# SCH_ATMEGA328_GAZPAR_rev1_0b.net
KiCad netlist of a schematic drawn in EasyEDA
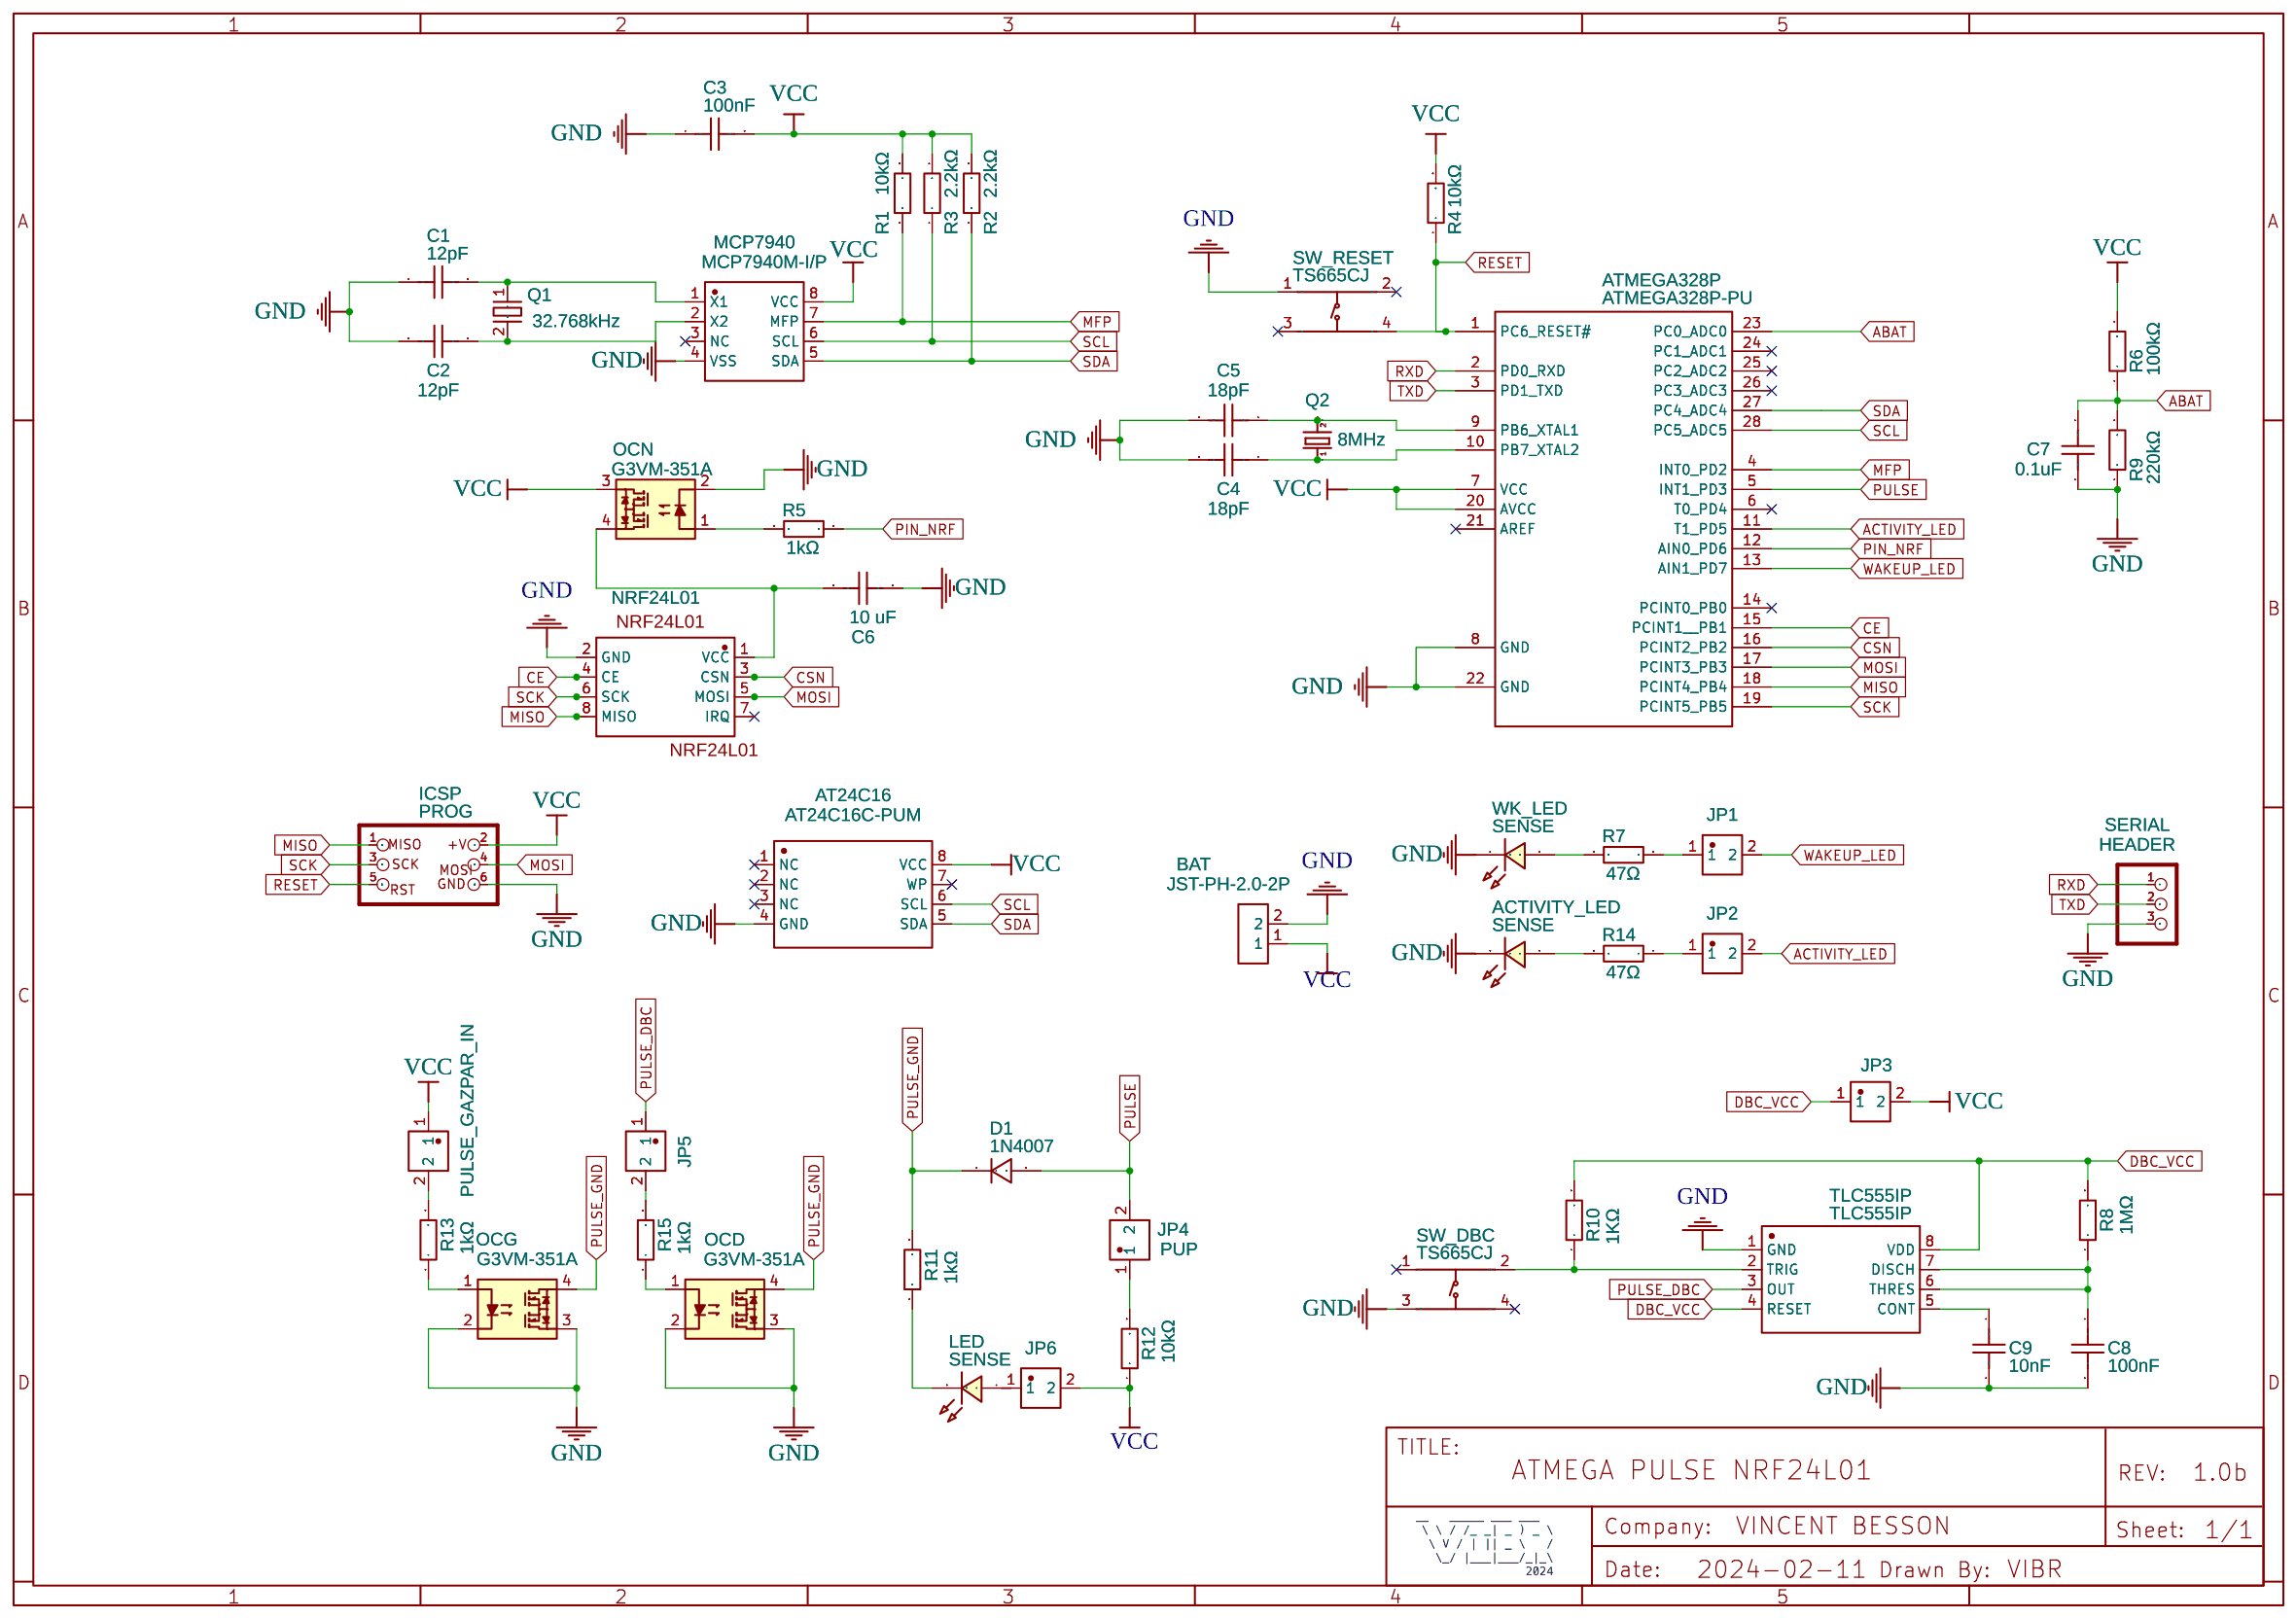
[diagram p0: schematic sheet]

(export (version "E")
  (design (tool "Eeschema 10.0.6"))
  (components
    (comp (ref "ACTIVITY_LED")
      (value "SENSE")
      (fields
        (field (name "Manufacturer Part") "333-2SURD/S530-A3")
        (field (name "Manufacturer") "EVERLIGHT(台湾亿光)")
      )
      (libsource (lib "") (part "LED-TH-5mm_R_2"))
    )
    (comp (ref "AT24C16")
      (value "AT24C16C-PUM")
      (fields (field (name "Manufacturer") "MICROCHIP(美国微芯)"))
      (libsource (lib "") (part "AT24C16C-PUM"))
    )
    (comp (ref "ATMEGA328P")
      (value "ATMEGA328P-PU")
      (fields (field (name "Manufacturer") "MICROCHIP(美国微芯)"))
      (libsource (lib "") (part "ATMEGA328P-PU"))
    )
    (comp (ref "BAT") (value "JST-PH-2.0-2P") (libsource (lib "") (part "JST-PH-2.0-2P")))
    (comp (ref "C1")
      (value "12pF")
      (fields
        (field (name "Manufacturer Part") "CC1H200KA1PDCH4B3003")
        (field (name "Manufacturer") "Dersonic(德尔创)")
      )
      (libsource (lib "") (part "CC1H200KA1PDCH4B3003"))
    )
    (comp (ref "C2")
      (value "12pF")
      (fields
        (field (name "Manufacturer Part") "CC1H200KA1PDCH4B3003")
        (field (name "Manufacturer") "Dersonic(德尔创)")
      )
      (libsource (lib "") (part "CC1H200KA1PDCH4B3003_1"))
    )
    (comp (ref "C3")
      (value "100nF")
      (fields
        (field (name "Manufacturer Part") "CC1H200KA1PDCH4B3003")
        (field (name "Manufacturer") "Dersonic(德尔创)")
      )
      (libsource (lib "") (part "CC1H200KA1PDCH4B3003"))
    )
    (comp (ref "C4")
      (value "18pF")
      (fields
        (field (name "Manufacturer Part") "CC1H200KA1PDCH4B3003")
        (field (name "Manufacturer") "Dersonic(德尔创)")
      )
      (libsource (lib "") (part "CC1H200KA1PDCH4B3003_1"))
    )
    (comp (ref "C5")
      (value "18pF")
      (fields
        (field (name "Manufacturer Part") "CC1H200KA1PDCH4B3003")
        (field (name "Manufacturer") "Dersonic(德尔创)")
      )
      (libsource (lib "") (part "CC1H200KA1PDCH4B3003_1"))
    )
    (comp (ref "C6")
      (value "10 uF")
      (fields
        (field (name "Manufacturer Part") "CC1H200KA1PDCH4B3003")
        (field (name "Manufacturer") "Dersonic(德尔创)")
      )
      (libsource (lib "") (part "CC1H200KA1PDCH4B3003"))
    )
    (comp (ref "C7")
      (value "0.1uF")
      (fields
        (field (name "Manufacturer Part") "CC1H200KA1PDCH4B3003")
        (field (name "Manufacturer") "Dersonic(德尔创)")
      )
      (libsource (lib "") (part "CC1H200KA1PDCH4B3003_2"))
    )
    (comp (ref "C8")
      (value "100nF")
      (fields
        (field (name "Manufacturer Part") "CC1H200KA1PDCH4B3003")
        (field (name "Manufacturer") "Dersonic(德尔创)")
      )
      (libsource (lib "") (part "CC1H200KA1PDCH4B3003_2"))
    )
    (comp (ref "C9")
      (value "10nF")
      (fields
        (field (name "Manufacturer Part") "CC1H200KA1PDCH4B3003")
        (field (name "Manufacturer") "Dersonic(德尔创)")
      )
      (libsource (lib "") (part "CC1H200KA1PDCH4B3003_2"))
    )
    (comp (ref "D1")
      (value "1N4007")
      (fields (field (name "Manufacturer") "SEMTECH"))
      (libsource (lib "") (part "1N4007"))
    )
    (comp (ref "ICSP") (value "PROG") (libsource (lib "") (part "CON_HEADER_PRG_AVR_ICSP-PTH")))
    (comp (ref "JP1")
      (value "GAZPAR")
      (fields
        (field (name "Manufacturer Part") "X6521WV-2x01H-C30D60")
        (field (name "Manufacturer") "XKB Connectivity(中国星坤)")
      )
      (libsource (lib "") (part "X6521WV-2X01H-C30D60_1"))
    )
    (comp (ref "JP2")
      (value "GAZPAR")
      (fields
        (field (name "Manufacturer Part") "X6521WV-2x01H-C30D60")
        (field (name "Manufacturer") "XKB Connectivity(中国星坤)")
      )
      (libsource (lib "") (part "X6521WV-2X01H-C30D60_1"))
    )
    (comp (ref "JP3")
      (value "GAZPAR")
      (fields
        (field (name "Manufacturer Part") "X6521WV-2x01H-C30D60")
        (field (name "Manufacturer") "XKB Connectivity(中国星坤)")
      )
      (libsource (lib "") (part "X6521WV-2X01H-C30D60_1"))
    )
    (comp (ref "JP4")
      (value "PUP")
      (fields
        (field (name "Manufacturer Part") "X6521WV-2x01H-C30D60")
        (field (name "Manufacturer") "XKB Connectivity(中国星坤)")
      )
      (libsource (lib "") (part "X6521WV-2X01H-C30D60"))
    )
    (comp (ref "JP5")
      (value "GAZPAR_PULSE")
      (fields
        (field (name "Manufacturer Part") "X6521WV-2x01H-C30D60")
        (field (name "Manufacturer") "XKB Connectivity(中国星坤)")
      )
      (libsource (lib "") (part "X6521WV-2X01H-C30D60_3"))
    )
    (comp (ref "JP6")
      (value "JMP_LED")
      (fields
        (field (name "Manufacturer Part") "X6521WV-2x01H-C30D60")
        (field (name "Manufacturer") "XKB Connectivity(中国星坤)")
      )
      (libsource (lib "") (part "X6521WV-2X01H-C30D60_1"))
    )
    (comp (ref "LED")
      (value "SENSE")
      (fields
        (field (name "Manufacturer Part") "333-2SURD/S530-A3")
        (field (name "Manufacturer") "EVERLIGHT(台湾亿光)")
      )
      (libsource (lib "") (part "LED-TH-5mm_R_1"))
    )
    (comp (ref "MCP7940")
      (value "MCP7940M-I/P")
      (fields (field (name "Manufacturer") "MICROCHIP(美国微芯)"))
      (libsource (lib "") (part "MCP7940M-I/P"))
    )
    (comp (ref "NRF24L01") (value "NRF24L01") (libsource (lib "") (part "NRF24L01")))
    (comp (ref "OCD") (value "G3VM-351A") (libsource (lib "") (part "G3VM-351A_1")))
    (comp (ref "OCG") (value "G3VM-351A") (libsource (lib "") (part "G3VM-351A")))
    (comp (ref "OCN") (value "G3VM-351A") (libsource (lib "") (part "G3VM-351A_2")))
    (comp (ref "PULSE_GAZPAR_IN")
      (value "GAZPAR_PULSE")
      (fields
        (field (name "Manufacturer Part") "X6521WV-2x01H-C30D60")
        (field (name "Manufacturer") "XKB Connectivity(中国星坤)")
      )
      (libsource (lib "") (part "X6521WV-2X01H-C30D60_2"))
    )
    (comp (ref "Q1")
      (value "32.768kHz")
      (fields (field (name "Manufacturer Part") "AB26T-32.768KHZ") (field (name "Manufacturer") "ABRACON"))
      (libsource (lib "") (part "AB26T-32.768KHZ"))
    )
    (comp (ref "Q2") (value "8MHz") (libsource (lib "") (part "HC49/S1.3")))
    (comp (ref "R1")
      (value "10kΩ")
      (fields
        (field (name "Manufacturer Part") "MFR0W4F1002A50")
        (field (name "Manufacturer") "UNI-ROYAL(厚声)")
      )
      (libsource (lib "") (part "MFR0W4F1002A50_1"))
    )
    (comp (ref "R2")
      (value "2.2kΩ")
      (fields
        (field (name "Manufacturer Part") "MFR0W4F1002A50")
        (field (name "Manufacturer") "UNI-ROYAL(厚声)")
      )
      (libsource (lib "") (part "MFR0W4F1002A50_1"))
    )
    (comp (ref "R3")
      (value "2.2kΩ")
      (fields
        (field (name "Manufacturer Part") "MFR0W4F1002A50")
        (field (name "Manufacturer") "UNI-ROYAL(厚声)")
      )
      (libsource (lib "") (part "MFR0W4F1002A50_1"))
    )
    (comp (ref "R4")
      (value "10kΩ")
      (fields
        (field (name "Manufacturer Part") "MFR0W4F1002A50")
        (field (name "Manufacturer") "UNI-ROYAL(厚声)")
      )
      (libsource (lib "") (part "MFR0W4F1002A50_1"))
    )
    (comp (ref "R5")
      (value "1kΩ")
      (fields
        (field (name "Manufacturer Part") "MFR0W4F1002A50")
        (field (name "Manufacturer") "UNI-ROYAL(厚声)")
      )
      (libsource (lib "") (part "MFR0W4F1002A50"))
    )
    (comp (ref "R6")
      (value "100kΩ")
      (fields
        (field (name "Manufacturer Part") "MFR0W4F1002A50")
        (field (name "Manufacturer") "UNI-ROYAL(厚声)")
      )
      (libsource (lib "") (part "MFR0W4F1002A50_1"))
    )
    (comp (ref "R7")
      (value "47Ω")
      (fields
        (field (name "Manufacturer Part") "MFR0W4F1002A50")
        (field (name "Manufacturer") "UNI-ROYAL(厚声)")
      )
      (libsource (lib "") (part "MFR0W4F1002A50"))
    )
    (comp (ref "R8")
      (value "1MΩ")
      (fields
        (field (name "Manufacturer Part") "MFR0W4F1002A50")
        (field (name "Manufacturer") "UNI-ROYAL(厚声)")
      )
      (libsource (lib "") (part "MFR0W4F1002A50_1"))
    )
    (comp (ref "R9")
      (value "220kΩ")
      (fields
        (field (name "Manufacturer Part") "MFR0W4F1002A50")
        (field (name "Manufacturer") "UNI-ROYAL(厚声)")
      )
      (libsource (lib "") (part "MFR0W4F1002A50_1"))
    )
    (comp (ref "R10")
      (value "1KΩ")
      (fields
        (field (name "Manufacturer Part") "MFR0W4F1002A50")
        (field (name "Manufacturer") "UNI-ROYAL(厚声)")
      )
      (libsource (lib "") (part "MFR0W4F1002A50_1"))
    )
    (comp (ref "R11")
      (value "1kΩ")
      (fields
        (field (name "Manufacturer Part") "MFR0W4F1002A50")
        (field (name "Manufacturer") "UNI-ROYAL(厚声)")
      )
      (libsource (lib "") (part "MFR0W4F1002A50_1"))
    )
    (comp (ref "R12")
      (value "10kΩ")
      (fields
        (field (name "Manufacturer Part") "MFR0W4F1002A50")
        (field (name "Manufacturer") "UNI-ROYAL(厚声)")
      )
      (libsource (lib "") (part "MFR0W4F1002A50_1"))
    )
    (comp (ref "R13")
      (value "1kΩ")
      (fields
        (field (name "Manufacturer Part") "MFR0W4F1002A50")
        (field (name "Manufacturer") "UNI-ROYAL(厚声)")
      )
      (libsource (lib "") (part "MFR0W4F1002A50_1"))
    )
    (comp (ref "R14")
      (value "47Ω")
      (fields
        (field (name "Manufacturer Part") "MFR0W4F1002A50")
        (field (name "Manufacturer") "UNI-ROYAL(厚声)")
      )
      (libsource (lib "") (part "MFR0W4F1002A50"))
    )
    (comp (ref "R15")
      (value "1kΩ")
      (fields
        (field (name "Manufacturer Part") "MFR0W4F1002A50")
        (field (name "Manufacturer") "UNI-ROYAL(厚声)")
      )
      (libsource (lib "") (part "MFR0W4F1002A50_1"))
    )
    (comp (ref "SERIAL") (value "HEADER") (libsource (lib "") (part "PINHD-1X3")))
    (comp (ref "SW_DBC")
      (value "TS665CJ")
      (fields (field (name "Manufacturer") "SHOU HAN(首韩)"))
      (libsource (lib "") (part "TS665CJ_1"))
    )
    (comp (ref "SW_RESET")
      (value "TS665CJ")
      (fields (field (name "Manufacturer") "SHOU HAN(首韩)"))
      (libsource (lib "") (part "TS665CJ"))
    )
    (comp (ref "TLC555IP")
      (value "TLC555IP")
      (fields (field (name "Manufacturer") "TI(德州仪器)"))
      (libsource (lib "") (part "TLC555IP"))
    )
    (comp (ref "WK_LED")
      (value "SENSE")
      (fields
        (field (name "Manufacturer Part") "333-2SURD/S530-A3")
        (field (name "Manufacturer") "EVERLIGHT(台湾亿光)")
      )
      (libsource (lib "") (part "LED-TH-5mm_R"))
    )
  )
  (nets
    (net (code "1") (name "ABAT") (class "Default")
      (node (ref "ATMEGA328P") (pin "23") (pinfunction "PC0_ADC0_23") (pintype "bidirectional"))
      (node (ref "C7") (pin "1") (pinfunction "1_1") (pintype "unspecified"))
      (node (ref "R6") (pin "1") (pinfunction "1_1") (pintype "input"))
      (node (ref "R9") (pin "2") (pinfunction "2_2") (pintype "input"))
    )
    (net (code "2") (name "ACTIVITY_LED") (class "Default")
      (node (ref "ATMEGA328P") (pin "11") (pinfunction "T1_PD5_11") (pintype "bidirectional"))
      (node (ref "JP2") (pin "2") (pinfunction "2_2") (pintype "unspecified"))
    )
    (net (code "3") (name "CE") (class "Default")
      (node (ref "ATMEGA328P") (pin "15") (pinfunction "PCINT1__PB1_15") (pintype "bidirectional"))
      (node (ref "NRF24L01") (pin "4") (pinfunction "CE_4") (pintype "unspecified"))
    )
    (net (code "4") (name "CSN") (class "Default")
      (node (ref "ATMEGA328P") (pin "16") (pinfunction "PCINT2_PB2_16") (pintype "bidirectional"))
      (node (ref "NRF24L01") (pin "3") (pinfunction "CSN_3") (pintype "unspecified"))
    )
    (net (code "5") (name "DBC_VCC") (class "Default")
      (node (ref "JP3") (pin "1") (pinfunction "1_1") (pintype "unspecified"))
      (node (ref "R10") (pin "2") (pinfunction "2_2") (pintype "input"))
      (node (ref "R8") (pin "2") (pinfunction "2_2") (pintype "input"))
      (node (ref "TLC555IP") (pin "4") (pinfunction "RESET_4") (pintype "unspecified"))
      (node (ref "TLC555IP") (pin "8") (pinfunction "VDD_8") (pintype "unspecified"))
    )
    (net (code "6") (name "GND") (class "Default")
      (node (ref "ACTIVITY_LED") (pin "2") (pinfunction "2_2") (pintype "unspecified"))
      (node (ref "AT24C16") (pin "4") (pinfunction "GND_4") (pintype "unspecified"))
      (node (ref "ATMEGA328P") (pin "22") (pinfunction "GND_22") (pintype "passive"))
      (node (ref "ATMEGA328P") (pin "8") (pinfunction "GND_8") (pintype "passive"))
      (node (ref "BAT") (pin "2") (pinfunction "2_2") (pintype "unspecified"))
      (node (ref "C1") (pin "1") (pinfunction "1_1") (pintype "unspecified"))
      (node (ref "C2") (pin "2") (pinfunction "2_2") (pintype "unspecified"))
      (node (ref "C3") (pin "1") (pinfunction "1_1") (pintype "unspecified"))
      (node (ref "C4") (pin "2") (pinfunction "2_2") (pintype "unspecified"))
      (node (ref "C5") (pin "2") (pinfunction "2_2") (pintype "unspecified"))
      (node (ref "C6") (pin "2") (pinfunction "2_2") (pintype "unspecified"))
      (node (ref "C7") (pin "2") (pinfunction "2_2") (pintype "unspecified"))
      (node (ref "C8") (pin "2") (pinfunction "2_2") (pintype "unspecified"))
      (node (ref "C9") (pin "2") (pinfunction "2_2") (pintype "unspecified"))
      (node (ref "ICSP") (pin "6") (pinfunction "GND_6") (pintype "unspecified"))
      (node (ref "MCP7940") (pin "4") (pinfunction "VSS_4") (pintype "unspecified"))
      (node (ref "NRF24L01") (pin "2") (pinfunction "GND_2") (pintype "unspecified"))
      (node (ref "OCD") (pin "2") (pintype "unspecified"))
      (node (ref "OCD") (pin "3") (pintype "unspecified"))
      (node (ref "OCG") (pin "2") (pintype "unspecified"))
      (node (ref "OCG") (pin "3") (pintype "unspecified"))
      (node (ref "OCN") (pin "2") (pintype "unspecified"))
      (node (ref "R9") (pin "1") (pinfunction "1_1") (pintype "input"))
      (node (ref "SERIAL") (pin "3") (pinfunction "3_3") (pintype "unspecified"))
      (node (ref "SW_DBC") (pin "3") (pinfunction "C_3") (pintype "unspecified"))
      (node (ref "SW_RESET") (pin "1") (pinfunction "A_1") (pintype "unspecified"))
      (node (ref "TLC555IP") (pin "1") (pinfunction "GND_1") (pintype "unspecified"))
      (node (ref "WK_LED") (pin "2") (pinfunction "2_2") (pintype "unspecified"))
    )
    (net (code "7") (name "MFP") (class "Default")
      (node (ref "ATMEGA328P") (pin "4") (pinfunction "INT0_PD2_4") (pintype "bidirectional"))
      (node (ref "MCP7940") (pin "7") (pinfunction "MFP_7") (pintype "unspecified"))
      (node (ref "R1") (pin "1") (pinfunction "1_1") (pintype "input"))
    )
    (net (code "8") (name "MISO") (class "Default")
      (node (ref "ATMEGA328P") (pin "18") (pinfunction "PCINT4_PB4_18") (pintype "bidirectional"))
      (node (ref "ICSP") (pin "1") (pinfunction "MISO_1") (pintype "unspecified"))
      (node (ref "NRF24L01") (pin "8") (pinfunction "MISO_8") (pintype "unspecified"))
    )
    (net (code "9") (name "MOSI") (class "Default")
      (node (ref "ATMEGA328P") (pin "17") (pinfunction "PCINT3_PB3_17") (pintype "bidirectional"))
      (node (ref "ICSP") (pin "4") (pinfunction "MOSI_4") (pintype "unspecified"))
      (node (ref "NRF24L01") (pin "5") (pinfunction "MOSI_5") (pintype "unspecified"))
    )
    (net (code "10") (name "Net-(ACTIVITY_LED-Pad1)") (class "Default")
      (node (ref "ACTIVITY_LED") (pin "1") (pinfunction "1_1") (pintype "unspecified"))
      (node (ref "R14") (pin "2") (pinfunction "2_2") (pintype "input"))
    )
    (net (code "11") (name "Net-(ATMEGA328P-PB6_XTAL1)") (class "Default")
      (node (ref "ATMEGA328P") (pin "9") (pinfunction "PB6_XTAL1_9") (pintype "bidirectional"))
      (node (ref "C5") (pin "1") (pinfunction "1_1") (pintype "unspecified"))
      (node (ref "Q2") (pin "2") (pinfunction "2_2") (pintype "bidirectional"))
    )
    (net (code "12") (name "Net-(ATMEGA328P-PB7_XTAL2)") (class "Default")
      (node (ref "ATMEGA328P") (pin "10") (pinfunction "PB7_XTAL2_10") (pintype "bidirectional"))
      (node (ref "C4") (pin "1") (pinfunction "1_1") (pintype "unspecified"))
      (node (ref "Q2") (pin "1") (pinfunction "1_1") (pintype "bidirectional"))
    )
    (net (code "13") (name "Net-(JP1-Pad1)") (class "Default")
      (node (ref "JP1") (pin "1") (pinfunction "1_1") (pintype "unspecified"))
      (node (ref "R7") (pin "1") (pinfunction "1_1") (pintype "input"))
    )
    (net (code "14") (name "Net-(JP2-Pad1)") (class "Default")
      (node (ref "JP2") (pin "1") (pinfunction "1_1") (pintype "unspecified"))
      (node (ref "R14") (pin "1") (pinfunction "1_1") (pintype "input"))
    )
    (net (code "15") (name "Net-(JP4-Pad1)") (class "Default")
      (node (ref "JP4") (pin "1") (pinfunction "1_1") (pintype "unspecified"))
      (node (ref "R12") (pin "2") (pinfunction "2_2") (pintype "input"))
    )
    (net (code "16") (name "Net-(JP5-Pad2)") (class "Default")
      (node (ref "JP5") (pin "2") (pinfunction "2_2") (pintype "unspecified"))
      (node (ref "R15") (pin "2") (pinfunction "2_2") (pintype "input"))
    )
    (net (code "17") (name "Net-(JP6-Pad1)") (class "Default")
      (node (ref "JP6") (pin "1") (pinfunction "1_1") (pintype "unspecified"))
      (node (ref "LED") (pin "1") (pinfunction "1_1") (pintype "unspecified"))
    )
    (net (code "18") (name "Net-(LED-Pad2)") (class "Default")
      (node (ref "LED") (pin "2") (pinfunction "2_2") (pintype "unspecified"))
      (node (ref "R11") (pin "1") (pinfunction "1_1") (pintype "input"))
    )
    (net (code "19") (name "Net-(MCP7940-X1)") (class "Default")
      (node (ref "C1") (pin "2") (pinfunction "2_2") (pintype "unspecified"))
      (node (ref "MCP7940") (pin "1") (pinfunction "X1_1") (pintype "unspecified"))
      (node (ref "Q1") (pin "1") (pinfunction "1_1") (pintype "input"))
    )
    (net (code "20") (name "Net-(MCP7940-X2)") (class "Default")
      (node (ref "C2") (pin "1") (pinfunction "1_1") (pintype "unspecified"))
      (node (ref "MCP7940") (pin "2") (pinfunction "X2_2") (pintype "unspecified"))
      (node (ref "Q1") (pin "2") (pinfunction "GND_2") (pintype "input"))
    )
    (net (code "21") (name "Net-(NRF24L01-VCC)") (class "Default")
      (node (ref "C6") (pin "1") (pinfunction "1_1") (pintype "unspecified"))
      (node (ref "NRF24L01") (pin "1") (pinfunction "VCC_1") (pintype "unspecified"))
      (node (ref "OCN") (pin "4") (pintype "unspecified"))
    )
    (net (code "22") (name "Net-(OCD-Pad1)") (class "Default")
      (node (ref "OCD") (pin "1") (pintype "unspecified"))
      (node (ref "R15") (pin "1") (pinfunction "1_1") (pintype "input"))
    )
    (net (code "23") (name "Net-(OCG-Pad1)") (class "Default")
      (node (ref "OCG") (pin "1") (pintype "unspecified"))
      (node (ref "R13") (pin "1") (pinfunction "1_1") (pintype "input"))
    )
    (net (code "24") (name "Net-(OCN-Pad1)") (class "Default")
      (node (ref "OCN") (pin "1") (pintype "unspecified"))
      (node (ref "R5") (pin "2") (pinfunction "2_2") (pintype "input"))
    )
    (net (code "25") (name "Net-(PULSE_GAZPAR_IN-Pad2)") (class "Default")
      (node (ref "PULSE_GAZPAR_IN") (pin "2") (pinfunction "2_2") (pintype "unspecified"))
      (node (ref "R13") (pin "2") (pinfunction "2_2") (pintype "input"))
    )
    (net (code "26") (name "Net-(R7-Pad2)") (class "Default")
      (node (ref "R7") (pin "2") (pinfunction "2_2") (pintype "input"))
      (node (ref "WK_LED") (pin "1") (pinfunction "1_1") (pintype "unspecified"))
    )
    (net (code "27") (name "Net-(SW_DBC-B)") (class "Default")
      (node (ref "R10") (pin "1") (pinfunction "1_1") (pintype "input"))
      (node (ref "SW_DBC") (pin "2") (pinfunction "B_2") (pintype "unspecified"))
      (node (ref "TLC555IP") (pin "2") (pinfunction "TRIG_2") (pintype "unspecified"))
    )
    (net (code "28") (name "Net-(TLC555IP-CONT)") (class "Default")
      (node (ref "C9") (pin "1") (pinfunction "1_1") (pintype "unspecified"))
      (node (ref "TLC555IP") (pin "5") (pinfunction "CONT_5") (pintype "unspecified"))
    )
    (net (code "29") (name "Net-(TLC555IP-DISCH)") (class "Default")
      (node (ref "C8") (pin "1") (pinfunction "1_1") (pintype "unspecified"))
      (node (ref "R8") (pin "1") (pinfunction "1_1") (pintype "input"))
      (node (ref "TLC555IP") (pin "6") (pinfunction "THRES_6") (pintype "unspecified"))
      (node (ref "TLC555IP") (pin "7") (pinfunction "DISCH_7") (pintype "unspecified"))
    )
    (net (code "30") (name "PIN_NRF") (class "Default")
      (node (ref "ATMEGA328P") (pin "12") (pinfunction "AIN0_PD6_12") (pintype "bidirectional"))
      (node (ref "R5") (pin "1") (pinfunction "1_1") (pintype "input"))
    )
    (net (code "31") (name "PULSE") (class "Default")
      (node (ref "ATMEGA328P") (pin "5") (pinfunction "INT1_PD3_5") (pintype "bidirectional"))
      (node (ref "D1") (pin "2") (pinfunction "2_2") (pintype "unspecified"))
      (node (ref "JP4") (pin "2") (pinfunction "2_2") (pintype "unspecified"))
    )
    (net (code "32") (name "PULSE_DBC") (class "Default")
      (node (ref "JP5") (pin "1") (pinfunction "1_1") (pintype "unspecified"))
      (node (ref "TLC555IP") (pin "3") (pinfunction "OUT_3") (pintype "unspecified"))
    )
    (net (code "33") (name "PULSE_GND") (class "Default")
      (node (ref "D1") (pin "1") (pinfunction "1_1") (pintype "unspecified"))
      (node (ref "OCD") (pin "4") (pintype "unspecified"))
      (node (ref "OCG") (pin "4") (pintype "unspecified"))
      (node (ref "R11") (pin "2") (pinfunction "2_2") (pintype "input"))
    )
    (net (code "34") (name "RESET") (class "Default")
      (node (ref "ATMEGA328P") (pin "1") (pinfunction "PC6_RESET#_1") (pintype "bidirectional"))
      (node (ref "ICSP") (pin "5") (pinfunction "RST_5") (pintype "unspecified"))
      (node (ref "R4") (pin "1") (pinfunction "1_1") (pintype "input"))
      (node (ref "SW_RESET") (pin "4") (pinfunction "D_4") (pintype "unspecified"))
    )
    (net (code "35") (name "RXD") (class "Default")
      (node (ref "ATMEGA328P") (pin "2") (pinfunction "PD0_RXD_2") (pintype "bidirectional"))
      (node (ref "SERIAL") (pin "1") (pinfunction "1_1") (pintype "unspecified"))
    )
    (net (code "36") (name "SCK") (class "Default")
      (node (ref "ATMEGA328P") (pin "19") (pinfunction "PCINT5_PB5_19") (pintype "bidirectional"))
      (node (ref "ICSP") (pin "3") (pinfunction "SCK_3") (pintype "unspecified"))
      (node (ref "NRF24L01") (pin "6") (pinfunction "SCK_6") (pintype "unspecified"))
    )
    (net (code "37") (name "SCL") (class "Default")
      (node (ref "AT24C16") (pin "6") (pinfunction "SCL_6") (pintype "unspecified"))
      (node (ref "ATMEGA328P") (pin "28") (pinfunction "PC5_ADC5_28") (pintype "bidirectional"))
      (node (ref "MCP7940") (pin "6") (pinfunction "SCL_6") (pintype "unspecified"))
      (node (ref "R3") (pin "1") (pinfunction "1_1") (pintype "input"))
    )
    (net (code "38") (name "SDA") (class "Default")
      (node (ref "AT24C16") (pin "5") (pinfunction "SDA_5") (pintype "unspecified"))
      (node (ref "ATMEGA328P") (pin "27") (pinfunction "PC4_ADC4_27") (pintype "bidirectional"))
      (node (ref "MCP7940") (pin "5") (pinfunction "SDA_5") (pintype "unspecified"))
      (node (ref "R2") (pin "1") (pinfunction "1_1") (pintype "input"))
    )
    (net (code "39") (name "TXD") (class "Default")
      (node (ref "ATMEGA328P") (pin "3") (pinfunction "PD1_TXD_3") (pintype "bidirectional"))
      (node (ref "SERIAL") (pin "2") (pinfunction "2_2") (pintype "unspecified"))
    )
    (net (code "40") (name "VCC") (class "Default")
      (node (ref "AT24C16") (pin "8") (pinfunction "VCC_8") (pintype "unspecified"))
      (node (ref "ATMEGA328P") (pin "20") (pinfunction "AVCC_20") (pintype "passive"))
      (node (ref "ATMEGA328P") (pin "7") (pinfunction "VCC_7") (pintype "passive"))
      (node (ref "BAT") (pin "1") (pinfunction "1_1") (pintype "unspecified"))
      (node (ref "C3") (pin "2") (pinfunction "2_2") (pintype "unspecified"))
      (node (ref "ICSP") (pin "2") (pinfunction "+V_2") (pintype "unspecified"))
      (node (ref "JP3") (pin "2") (pinfunction "2_2") (pintype "unspecified"))
      (node (ref "JP6") (pin "2") (pinfunction "2_2") (pintype "unspecified"))
      (node (ref "MCP7940") (pin "8") (pinfunction "VCC_8") (pintype "unspecified"))
      (node (ref "OCN") (pin "3") (pintype "unspecified"))
      (node (ref "PULSE_GAZPAR_IN") (pin "1") (pinfunction "1_1") (pintype "unspecified"))
      (node (ref "R1") (pin "2") (pinfunction "2_2") (pintype "input"))
      (node (ref "R12") (pin "1") (pinfunction "1_1") (pintype "input"))
      (node (ref "R2") (pin "2") (pinfunction "2_2") (pintype "input"))
      (node (ref "R3") (pin "2") (pinfunction "2_2") (pintype "input"))
      (node (ref "R4") (pin "2") (pinfunction "2_2") (pintype "input"))
      (node (ref "R6") (pin "2") (pinfunction "2_2") (pintype "input"))
    )
    (net (code "41") (name "WAKEUP_LED") (class "Default")
      (node (ref "ATMEGA328P") (pin "13") (pinfunction "AIN1_PD7_13") (pintype "bidirectional"))
      (node (ref "JP1") (pin "2") (pinfunction "2_2") (pintype "unspecified"))
    )
    (net (code "42") (name "unconnected-(AT24C16-NC-Pad1)") (class "Default")
      (node (ref "AT24C16") (pin "1") (pinfunction "NC_1") (pintype "unspecified+no_connect"))
    )
    (net (code "43") (name "unconnected-(AT24C16-NC-Pad2)") (class "Default")
      (node (ref "AT24C16") (pin "2") (pinfunction "NC_2") (pintype "unspecified+no_connect"))
    )
    (net (code "44") (name "unconnected-(AT24C16-NC-Pad3)") (class "Default")
      (node (ref "AT24C16") (pin "3") (pinfunction "NC_3") (pintype "unspecified+no_connect"))
    )
    (net (code "45") (name "unconnected-(AT24C16-WP-Pad7)") (class "Default")
      (node (ref "AT24C16") (pin "7") (pinfunction "WP_7") (pintype "unspecified+no_connect"))
    )
    (net (code "46") (name "unconnected-(ATMEGA328P-AREF-Pad21)") (class "Default")
      (node (ref "ATMEGA328P") (pin "21") (pinfunction "AREF_21") (pintype "passive+no_connect"))
    )
    (net (code "47") (name "unconnected-(ATMEGA328P-PC1_ADC1-Pad24)") (class "Default")
      (node (ref "ATMEGA328P") (pin "24") (pinfunction "PC1_ADC1_24") (pintype "bidirectional+no_connect"))
    )
    (net (code "48") (name "unconnected-(ATMEGA328P-PC2_ADC2-Pad25)") (class "Default")
      (node (ref "ATMEGA328P") (pin "25") (pinfunction "PC2_ADC2_25") (pintype "bidirectional+no_connect"))
    )
    (net (code "49") (name "unconnected-(ATMEGA328P-PC3_ADC3-Pad26)") (class "Default")
      (node (ref "ATMEGA328P") (pin "26") (pinfunction "PC3_ADC3_26") (pintype "bidirectional+no_connect"))
    )
    (net (code "50") (name "unconnected-(ATMEGA328P-PCINT0_PB0-Pad14)") (class "Default")
      (node (ref "ATMEGA328P") (pin "14") (pinfunction "PCINT0_PB0_14") (pintype "bidirectional+no_connect"))
    )
    (net (code "51") (name "unconnected-(ATMEGA328P-T0_PD4-Pad6)") (class "Default")
      (node (ref "ATMEGA328P") (pin "6") (pinfunction "T0_PD4_6") (pintype "bidirectional+no_connect"))
    )
    (net (code "52") (name "unconnected-(MCP7940-NC-Pad3)") (class "Default")
      (node (ref "MCP7940") (pin "3") (pinfunction "NC_3") (pintype "unspecified+no_connect"))
    )
    (net (code "53") (name "unconnected-(NRF24L01-IRQ-Pad7)") (class "Default")
      (node (ref "NRF24L01") (pin "7") (pinfunction "IRQ_7") (pintype "unspecified+no_connect"))
    )
    (net (code "54") (name "unconnected-(SW_DBC-A-Pad1)") (class "Default")
      (node (ref "SW_DBC") (pin "1") (pinfunction "A_1") (pintype "unspecified+no_connect"))
    )
    (net (code "55") (name "unconnected-(SW_DBC-D-Pad4)") (class "Default")
      (node (ref "SW_DBC") (pin "4") (pinfunction "D_4") (pintype "unspecified+no_connect"))
    )
    (net (code "56") (name "unconnected-(SW_RESET-B-Pad2)") (class "Default")
      (node (ref "SW_RESET") (pin "2") (pinfunction "B_2") (pintype "unspecified+no_connect"))
    )
    (net (code "57") (name "unconnected-(SW_RESET-C-Pad3)") (class "Default")
      (node (ref "SW_RESET") (pin "3") (pinfunction "C_3") (pintype "unspecified+no_connect"))
    )
  )
)
